# Grove_-_Relay_v1_2.net
KiCad netlist of a schematic drawn in EAGLE
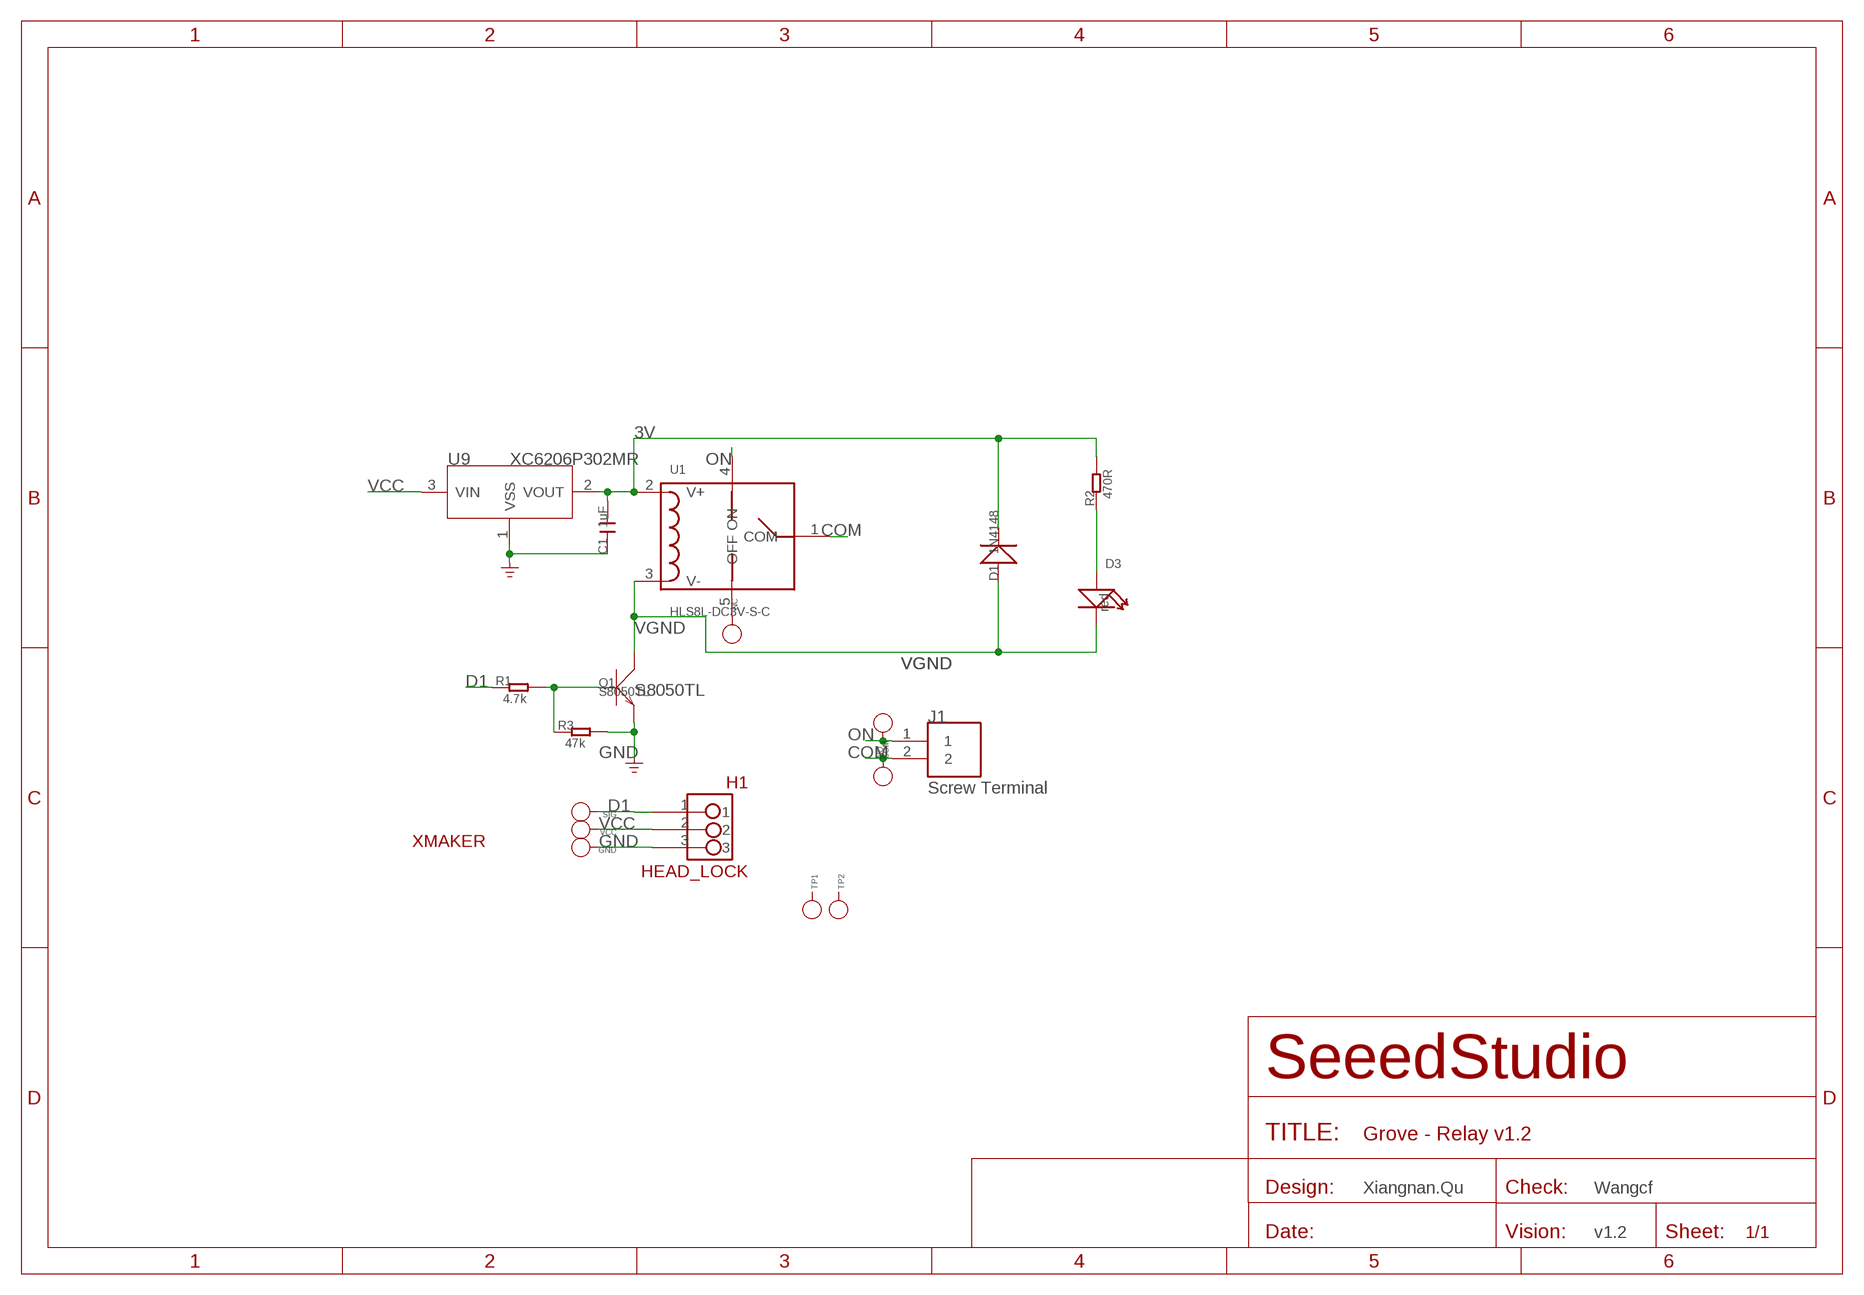
[diagram p0: schematic, sheet 1]

(export (version "E")
  (design (tool "Eeschema 10.0.6"))
  (components
    (comp (ref "C1")
      (value "1uF")
      (footprint "eagle-import:C0603")
      (libsource (lib "eagle-import") (part "C-0603"))
    )
    (comp (ref "COM")
      (value "PAD-TEST-POINT'4545'")
      (footprint "eagle-import:TP_4545")
      (fields (field (name "PARTNO") "DNP"))
      (libsource (lib "eagle-import") (part "PAD-TEST-POINT'4545'"))
    )
    (comp (ref "D1")
      (value "1N4148")
      (footprint "eagle-import:LL-34")
      (libsource (lib "eagle-import") (part "D'1N4148-SMD'"))
    )
    (comp (ref "D3")
      (value "red")
      (footprint "eagle-import:LED-0603")
      (libsource (lib "eagle-import") (part "LED'0603'"))
    )
    (comp (ref "GND")
      (value "PAD-TEST-POINT'4545'")
      (footprint "eagle-import:TP_4545")
      (fields (field (name "PARTNO") "DNP"))
      (libsource (lib "eagle-import") (part "PAD-TEST-POINT'4545'"))
    )
    (comp (ref "H1")
      (value "HEAD_LOCK")
      (footprint "eagle-import:HEAD_LOCK")
      (libsource (lib "eagle-import") (part "HEAD_LOCK"))
    )
    (comp (ref "J1")
      (value "Screw Terminal")
      (footprint "eagle-import:CON2")
      (libsource (lib "eagle-import") (part "CON2"))
    )
    (comp (ref "NC")
      (value "PAD-TEST-POINT'4545'")
      (footprint "eagle-import:TP_4545")
      (fields (field (name "PARTNO") "DNP"))
      (libsource (lib "eagle-import") (part "PAD-TEST-POINT'4545'"))
    )
    (comp (ref "NO")
      (value "PAD-TEST-POINT'4545'")
      (footprint "eagle-import:TP_4545")
      (fields (field (name "PARTNO") "DNP"))
      (libsource (lib "eagle-import") (part "PAD-TEST-POINT'4545'"))
    )
    (comp (ref "Q1")
      (value "S8050TL")
      (footprint "eagle-import:SOT23")
      (libsource (lib "eagle-import") (part "TRANSISTOR-NPN-SOT23"))
    )
    (comp (ref "R1")
      (value "4.7k")
      (footprint "eagle-import:R0603")
      (libsource (lib "eagle-import") (part "R-0603"))
    )
    (comp (ref "R2")
      (value "470R")
      (footprint "eagle-import:R0603")
      (libsource (lib "eagle-import") (part "R-0603"))
    )
    (comp (ref "R3")
      (value "47k")
      (footprint "eagle-import:R0603")
      (libsource (lib "eagle-import") (part "R-0603"))
    )
    (comp (ref "SIG")
      (value "PAD-TEST-POINT'4545'")
      (footprint "eagle-import:TP_4545")
      (fields (field (name "PARTNO") "DNP"))
      (libsource (lib "eagle-import") (part "PAD-TEST-POINT'4545'"))
    )
    (comp (ref "TP1")
      (value "PAD-TEST-POINT'4545'")
      (footprint "eagle-import:TP_4545")
      (fields (field (name "PARTNO") "DNP"))
      (libsource (lib "eagle-import") (part "PAD-TEST-POINT'4545'"))
    )
    (comp (ref "TP2")
      (value "PAD-TEST-POINT'4545'")
      (footprint "eagle-import:TP_4545")
      (fields (field (name "PARTNO") "DNP"))
      (libsource (lib "eagle-import") (part "PAD-TEST-POINT'4545'"))
    )
    (comp (ref "U$5")
      (value "XMAKERLOGO2")
      (footprint "eagle-import:XMAKERLOGO2")
      (libsource (lib "eagle-import") (part "XMAKERLOGO2"))
    )
    (comp (ref "U1")
      (value "HLS8L-DC3V-S-C")
      (footprint "eagle-import:RELAY")
      (libsource (lib "eagle-import") (part "RELAY"))
    )
    (comp (ref "U9")
      (value "XC6206P302MR")
      (footprint "eagle-import:SOT23")
      (libsource (lib "eagle-import") (part "XC6206MR"))
    )
    (comp (ref "VCC")
      (value "PAD-TEST-POINT'4545'")
      (footprint "eagle-import:TP_4545")
      (fields (field (name "PARTNO") "DNP"))
      (libsource (lib "eagle-import") (part "PAD-TEST-POINT'4545'"))
    )
  )
  (nets
    (net (code "1") (name "/3V") (class "Default")
      (node (ref "C1") (pin "2") (pinfunction "2_2") (pintype "passive"))
      (node (ref "D1") (pin "C") (pinfunction "-_C") (pintype "passive"))
      (node (ref "R2") (pin "2") (pinfunction "2_2") (pintype "passive"))
      (node (ref "U1") (pin "2") (pinfunction "V+_2") (pintype "bidirectional"))
      (node (ref "U9") (pin "2") (pinfunction "VOUT_2") (pintype "output"))
    )
    (net (code "2") (name "/COM") (class "Default")
      (node (ref "COM") (pin "T") (pinfunction "T_T") (pintype "bidirectional"))
      (node (ref "J1") (pin "2") (pinfunction "2_2") (pintype "bidirectional"))
      (node (ref "U1") (pin "1") (pinfunction "COM_1") (pintype "bidirectional"))
    )
    (net (code "3") (name "/D1") (class "Default")
      (node (ref "H1") (pin "1") (pinfunction "1_1") (pintype "passive"))
      (node (ref "R1") (pin "1") (pinfunction "1_1") (pintype "passive"))
      (node (ref "SIG") (pin "T") (pinfunction "T_T") (pintype "bidirectional"))
    )
    (net (code "4") (name "/ON") (class "Default")
      (node (ref "J1") (pin "1") (pinfunction "1_1") (pintype "bidirectional"))
      (node (ref "NO") (pin "T") (pinfunction "T_T") (pintype "bidirectional"))
      (node (ref "U1") (pin "4") (pinfunction "ON_4") (pintype "bidirectional"))
    )
    (net (code "5") (name "/VCC") (class "Default")
      (node (ref "H1") (pin "2") (pinfunction "2_2") (pintype "passive"))
      (node (ref "U9") (pin "3") (pinfunction "VIN_3") (pintype "input"))
      (node (ref "VCC") (pin "T") (pinfunction "T_T") (pintype "bidirectional"))
    )
    (net (code "6") (name "/VGND") (class "Default")
      (node (ref "D1") (pin "A") (pinfunction "+_A") (pintype "passive"))
      (node (ref "D3") (pin "-") (pinfunction "-_-") (pintype "passive"))
      (node (ref "Q1") (pin "3") (pinfunction "C_3") (pintype "passive"))
      (node (ref "U1") (pin "3") (pinfunction "V-_3") (pintype "bidirectional"))
    )
    (net (code "7") (name "GND_POWER") (class "Default")
      (node (ref "C1") (pin "1") (pinfunction "1_1") (pintype "passive"))
      (node (ref "GND") (pin "T") (pinfunction "T_T") (pintype "bidirectional"))
      (node (ref "H1") (pin "3") (pinfunction "3_3") (pintype "passive"))
      (node (ref "Q1") (pin "2") (pinfunction "E_2") (pintype "passive"))
      (node (ref "R3") (pin "2") (pinfunction "2_2") (pintype "passive"))
      (node (ref "U9") (pin "1") (pinfunction "VSS_1") (pintype "power_in"))
    )
    (net (code "8") (name "Net-(D3-Pad+)") (class "Default")
      (node (ref "D3") (pin "+") (pinfunction "+_+") (pintype "passive"))
      (node (ref "R2") (pin "1") (pinfunction "1_1") (pintype "passive"))
    )
    (net (code "9") (name "Net-(Q1-B)") (class "Default")
      (node (ref "Q1") (pin "1") (pinfunction "B_1") (pintype "passive"))
      (node (ref "R1") (pin "2") (pinfunction "2_2") (pintype "passive"))
      (node (ref "R3") (pin "1") (pinfunction "1_1") (pintype "passive"))
    )
    (net (code "10") (name "Net-(U1-OFF)") (class "Default")
      (node (ref "NC") (pin "T") (pinfunction "T_T") (pintype "bidirectional"))
      (node (ref "U1") (pin "5") (pinfunction "OFF_5") (pintype "bidirectional"))
    )
    (net (code "11") (name "unconnected-(TP1-PadT)") (class "Default")
      (node (ref "TP1") (pin "T") (pinfunction "T_T") (pintype "bidirectional"))
    )
    (net (code "12") (name "unconnected-(TP2-PadT)") (class "Default")
      (node (ref "TP2") (pin "T") (pinfunction "T_T") (pintype "bidirectional"))
    )
  )
)
